# PotentiometerDaughter.net
KiCad netlist of a schematic drawn in Altium Designer
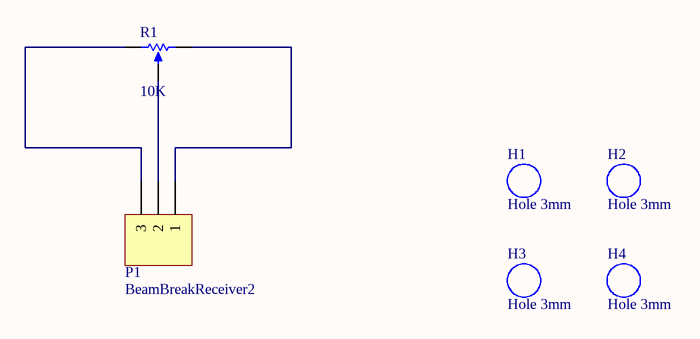
[diagram p0: PotentiometerDaughter.SchDoc]

(export (version "E")
  (design (tool "Eeschema 10.0.6"))
  (components
    (comp (ref "H1")
      (value "Hole 3mm")
      (footprint "Hole 3mm")
      (libsource (lib "ECE Lib 22") (part "Hole 3mm"))
    )
    (comp (ref "H2")
      (value "Hole 3mm")
      (footprint "Hole 3mm")
      (libsource (lib "ECE Lib 22") (part "Hole 3mm"))
    )
    (comp (ref "H3")
      (value "Hole 3mm")
      (footprint "Hole 3mm")
      (libsource (lib "ECE Lib 22") (part "Hole 3mm"))
    )
    (comp (ref "H4")
      (value "Hole 3mm")
      (footprint "Hole 3mm")
      (libsource (lib "ECE Lib 22") (part "Hole 3mm"))
    )
    (comp (ref "P1")
      (value "BeamBreakReceiver2")
      (footprint "HDR1X3")
      (description "Header, 3-Pin")
      (fields (field (name "PUBLISHER") "Altium Limited"))
      (libsource (lib "Miscellaneous Connectors") (part "Header 3"))
    )
    (comp (ref "R1")
      (value "10K")
      (footprint "POT OFFSET 400")
      (description "Potentiometer")
      (fields (field (name "Comment") "RPot_4") (field (name "PUBLISHER") "Altium Limited"))
      (libsource (lib "ECE Lib 22") (part "RPot_2"))
    )
  )
  (nets
    (net (code "1") (name "Net-(R1-BOT)") (class "Default")
      (node (ref "P1") (pin "1") (pinfunction "1_1") (pintype "passive"))
      (node (ref "R1") (pin "3") (pinfunction "BOT_3") (pintype "passive"))
    )
    (net (code "2") (name "Net-(R1-TAP)") (class "Default")
      (node (ref "P1") (pin "2") (pinfunction "2_2") (pintype "passive"))
      (node (ref "R1") (pin "2") (pinfunction "TAP_2") (pintype "passive"))
    )
    (net (code "3") (name "Net-(R1-TOP)") (class "Default")
      (node (ref "P1") (pin "3") (pinfunction "3_3") (pintype "passive"))
      (node (ref "R1") (pin "1") (pinfunction "TOP_1") (pintype "passive"))
    )
  )
)
